# OPAMP_TESTER_1.net
KiCad netlist of a schematic drawn in Altium Designer
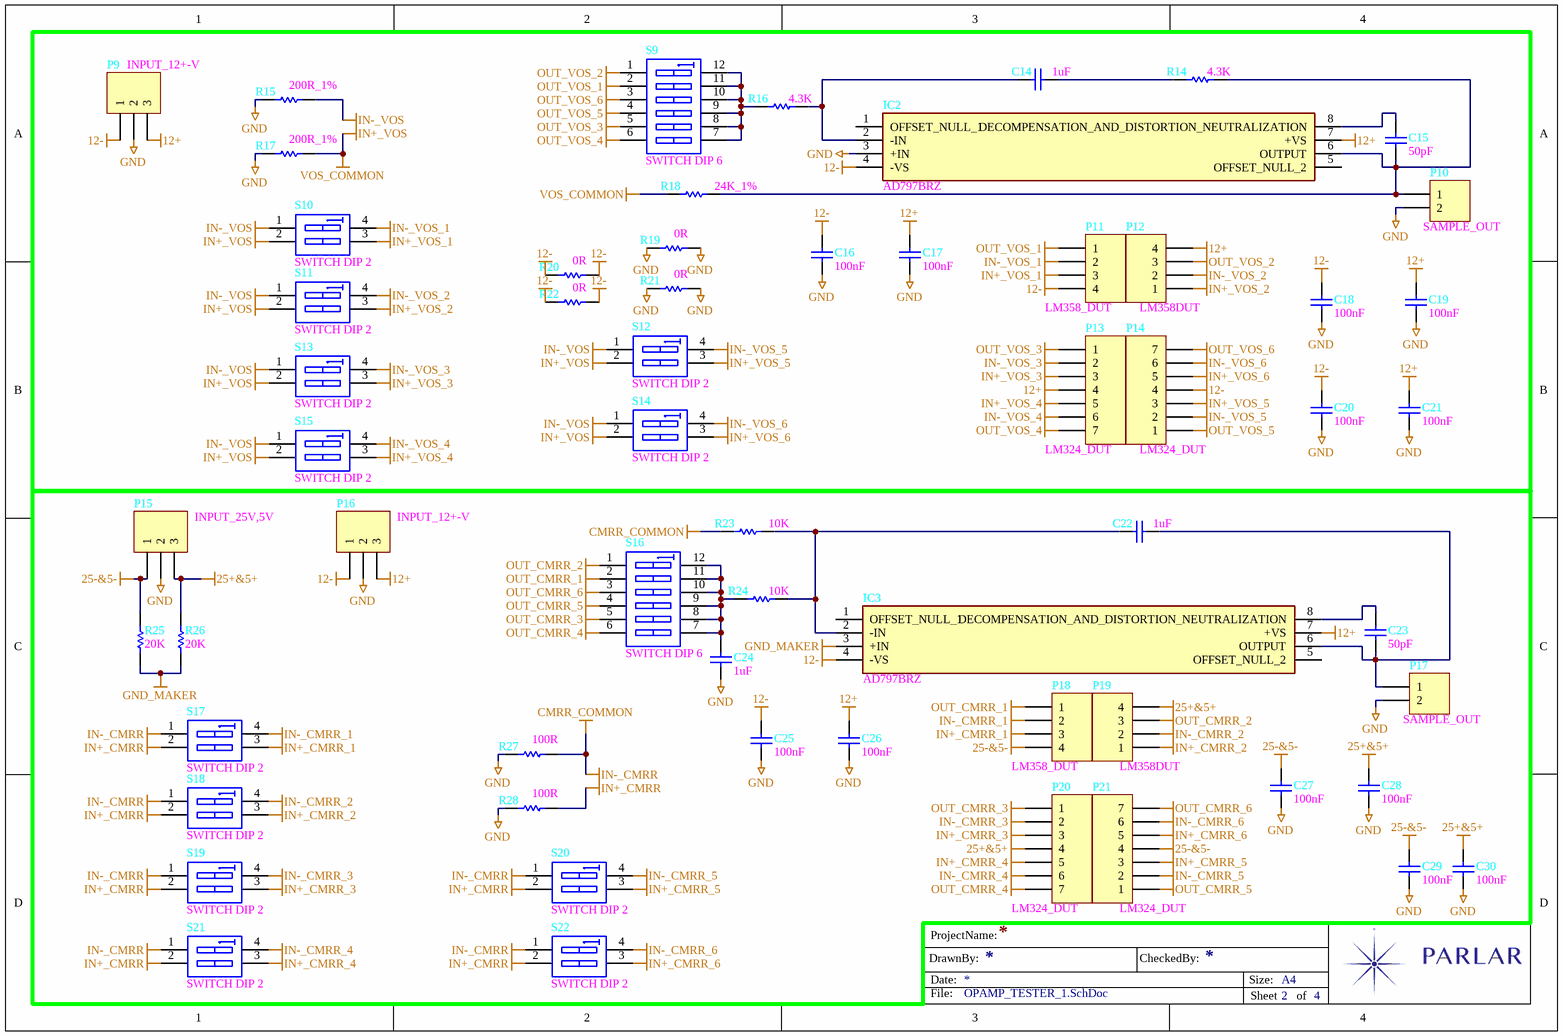
[diagram p0: OPAMP_TESTER_1.SchDoc]

(export (version "E")
  (design (tool "Eeschema 10.0.6"))
  (components
    (comp (ref "C14")
      (value "1uF")
      (footprint "SMD 1206")
      (description "Capacitor")
      (fields (field (name "PUBLISHER") "Altium Limited"))
      (libsource (lib "Parlarlib_30") (part "CAP"))
    )
    (comp (ref "C15")
      (value "50pF")
      (footprint "SMD 1206")
      (description "Capacitor")
      (fields (field (name "PUBLISHER") "Altium Limited"))
      (libsource (lib "Parlarlib_30") (part "CAP"))
    )
    (comp (ref "C16")
      (value "100nF")
      (footprint "SMD 0805")
      (description "Capacitor")
      (fields (field (name "PUBLISHER") "Altium Limited"))
      (libsource (lib "Parlarlib_30") (part "CAP"))
    )
    (comp (ref "C17")
      (value "100nF")
      (footprint "SMD 0805")
      (description "Capacitor")
      (fields (field (name "PUBLISHER") "Altium Limited"))
      (libsource (lib "Parlarlib_30") (part "CAP"))
    )
    (comp (ref "C18")
      (value "100nF")
      (footprint "SMD 0805")
      (description "Capacitor")
      (fields (field (name "PUBLISHER") "Altium Limited"))
      (libsource (lib "Parlarlib_30") (part "CAP"))
    )
    (comp (ref "C19")
      (value "100nF")
      (footprint "SMD 0805")
      (description "Capacitor")
      (fields (field (name "PUBLISHER") "Altium Limited"))
      (libsource (lib "Parlarlib_30") (part "CAP"))
    )
    (comp (ref "C20")
      (value "100nF")
      (footprint "SMD 0805")
      (description "Capacitor")
      (fields (field (name "PUBLISHER") "Altium Limited"))
      (libsource (lib "Parlarlib_30") (part "CAP"))
    )
    (comp (ref "C21")
      (value "100nF")
      (footprint "SMD 0805")
      (description "Capacitor")
      (fields (field (name "PUBLISHER") "Altium Limited"))
      (libsource (lib "Parlarlib_30") (part "CAP"))
    )
    (comp (ref "C22")
      (value "1uF")
      (footprint "SMD 1206")
      (description "Capacitor")
      (fields (field (name "PUBLISHER") "Altium Limited"))
      (libsource (lib "Parlarlib_30") (part "CAP"))
    )
    (comp (ref "C23")
      (value "50pF")
      (footprint "SMD 1206")
      (description "Capacitor")
      (fields (field (name "PUBLISHER") "Altium Limited"))
      (libsource (lib "Parlarlib_30") (part "CAP"))
    )
    (comp (ref "C24")
      (value "1uF")
      (footprint "SMD 0805")
      (description "Capacitor")
      (fields (field (name "PUBLISHER") "Altium Limited"))
      (libsource (lib "Parlarlib_30") (part "CAP"))
    )
    (comp (ref "C25")
      (value "100nF")
      (footprint "SMD 0805")
      (description "Capacitor")
      (fields (field (name "PUBLISHER") "Altium Limited"))
      (libsource (lib "Parlarlib_30") (part "CAP"))
    )
    (comp (ref "C26")
      (value "100nF")
      (footprint "SMD 0805")
      (description "Capacitor")
      (fields (field (name "PUBLISHER") "Altium Limited"))
      (libsource (lib "Parlarlib_30") (part "CAP"))
    )
    (comp (ref "C27")
      (value "100nF")
      (footprint "SMD 0805")
      (description "Capacitor")
      (fields (field (name "PUBLISHER") "Altium Limited"))
      (libsource (lib "Parlarlib_30") (part "CAP"))
    )
    (comp (ref "C28")
      (value "100nF")
      (footprint "SMD 0805")
      (description "Capacitor")
      (fields (field (name "PUBLISHER") "Altium Limited"))
      (libsource (lib "Parlarlib_30") (part "CAP"))
    )
    (comp (ref "C29")
      (value "100nF")
      (footprint "SMD 0805")
      (description "Capacitor")
      (fields (field (name "PUBLISHER") "Altium Limited"))
      (libsource (lib "Parlarlib_30") (part "CAP"))
    )
    (comp (ref "C30")
      (value "100nF")
      (footprint "SMD 0805")
      (description "Capacitor")
      (fields (field (name "PUBLISHER") "Altium Limited"))
      (libsource (lib "Parlarlib_30") (part "CAP"))
    )
    (comp (ref "IC2")
      (value "AD797BRZ")
      (footprint "SamacSys:SOIC127P600X175-8N")
      (description "Integrated Circuit")
      (fields (field (name "MOUSER PART NUMBER") "584-AD797BRZ"))
      (libsource (lib "*") (part "AD797BRZ"))
    )
    (comp (ref "IC3")
      (value "AD797BRZ")
      (footprint "SamacSys:SOIC127P600X175-8N")
      (description "Integrated Circuit")
      (fields (field (name "MOUSER PART NUMBER") "584-AD797BRZ"))
      (libsource (lib "*") (part "AD797BRZ"))
    )
    (comp (ref "P9")
      (value "INPUT_12+-V")
      (footprint "CON XH 3")
      (description "Header, 3-Pin")
      (fields (field (name "PUBLISHER") "Altium Limited"))
      (libsource (lib "Parlarlib_30") (part "CONNECTOR 3"))
    )
    (comp (ref "P10")
      (value "SAMPLE_OUT")
      (footprint "CON XH 2")
      (description "Header, 2-Pin")
      (fields (field (name "PUBLISHER") "Altium Limited"))
      (libsource (lib "Parlarlib_30") (part "CONNECTOR 2"))
    )
    (comp (ref "P11")
      (value "LM358_DUT")
      (footprint "CON HDR 2.54FM 4")
      (description "Header, 4-Pin")
      (fields (field (name "PUBLISHER") "Altium Limited"))
      (libsource (lib "Parlarlib_30") (part "CONNECTOR 4"))
    )
    (comp (ref "P12")
      (value "LM358DUT")
      (footprint "CON HDR 2.54FM 4")
      (description "Header, 4-Pin")
      (fields (field (name "PUBLISHER") "Altium Limited"))
      (libsource (lib "") (part "CONNECTOR 4_1"))
    )
    (comp (ref "P13")
      (value "LM324_DUT")
      (footprint "CON HDR 2.54FM 7")
      (description "Header, 7-Pin")
      (fields (field (name "PUBLISHER") "Altium Limited"))
      (libsource (lib "") (part "CONNECTOR 7_1"))
    )
    (comp (ref "P14")
      (value "LM324_DUT")
      (footprint "CON HDR 2.54FM 7")
      (description "Header, 7-Pin")
      (fields (field (name "PUBLISHER") "Altium Limited"))
      (libsource (lib "Parlarlib_30") (part "CONNECTOR 7"))
    )
    (comp (ref "P15")
      (value "INPUT_25V,5V")
      (footprint "CON XH 3")
      (description "Header, 3-Pin")
      (fields (field (name "PUBLISHER") "Altium Limited"))
      (libsource (lib "Parlarlib_30") (part "CONNECTOR 3"))
    )
    (comp (ref "P16")
      (value "INPUT_12+-V")
      (footprint "CON XH 3")
      (description "Header, 3-Pin")
      (fields (field (name "PUBLISHER") "Altium Limited"))
      (libsource (lib "Parlarlib_30") (part "CONNECTOR 3"))
    )
    (comp (ref "P17")
      (value "SAMPLE_OUT")
      (footprint "CON XH 2")
      (description "Header, 2-Pin")
      (fields (field (name "PUBLISHER") "Altium Limited"))
      (libsource (lib "Parlarlib_30") (part "CONNECTOR 2"))
    )
    (comp (ref "P18")
      (value "LM358_DUT")
      (footprint "CON HDR 2.54FM 4")
      (description "Header, 4-Pin")
      (fields (field (name "PUBLISHER") "Altium Limited"))
      (libsource (lib "Parlarlib_30") (part "CONNECTOR 4"))
    )
    (comp (ref "P19")
      (value "LM358DUT")
      (footprint "CON HDR 2.54FM 4")
      (description "Header, 4-Pin")
      (fields (field (name "PUBLISHER") "Altium Limited"))
      (libsource (lib "") (part "CONNECTOR 4_1"))
    )
    (comp (ref "P20")
      (value "LM324_DUT")
      (footprint "CON HDR 2.54FM 7")
      (description "Header, 7-Pin")
      (fields (field (name "PUBLISHER") "Altium Limited"))
      (libsource (lib "") (part "CONNECTOR 7_1"))
    )
    (comp (ref "P21")
      (value "LM324_DUT")
      (footprint "CON HDR 2.54FM 7")
      (description "Header, 7-Pin")
      (fields (field (name "PUBLISHER") "Altium Limited"))
      (libsource (lib "Parlarlib_30") (part "CONNECTOR 7"))
    )
    (comp (ref "R14")
      (value "4.3K")
      (footprint "SMD 0805")
      (description "Resistor")
      (libsource (lib "Parlarlib_30") (part "RES"))
    )
    (comp (ref "R15")
      (value "200R_1%")
      (footprint "SMD 0805")
      (description "Resistor")
      (libsource (lib "Parlarlib_30") (part "RES"))
    )
    (comp (ref "R16")
      (value "4.3K")
      (footprint "SMD 1206")
      (description "Resistor")
      (libsource (lib "Parlarlib_30") (part "RES"))
    )
    (comp (ref "R17")
      (value "200R_1%")
      (footprint "SMD 0805")
      (description "Resistor")
      (libsource (lib "Parlarlib_30") (part "RES"))
    )
    (comp (ref "R18")
      (value "24K_1%")
      (footprint "SMD 0805")
      (description "Resistor")
      (libsource (lib "Parlarlib_30") (part "RES"))
    )
    (comp (ref "R19")
      (value "0R")
      (footprint "SMD 1206")
      (description "Resistor")
      (libsource (lib "Parlarlib_30") (part "RES"))
    )
    (comp (ref "R20")
      (value "0R")
      (footprint "SMD 1206")
      (description "Resistor")
      (libsource (lib "Parlarlib_30") (part "RES"))
    )
    (comp (ref "R21")
      (value "0R")
      (footprint "SMD 1206")
      (description "Resistor")
      (libsource (lib "Parlarlib_30") (part "RES"))
    )
    (comp (ref "R22")
      (value "0R")
      (footprint "SMD 1206")
      (description "Resistor")
      (libsource (lib "Parlarlib_30") (part "RES"))
    )
    (comp (ref "R23")
      (value "10K")
      (footprint "SMD 0805")
      (description "Resistor")
      (libsource (lib "Parlarlib_30") (part "RES"))
    )
    (comp (ref "R24")
      (value "10K")
      (footprint "SMD 0805")
      (description "Resistor")
      (libsource (lib "Parlarlib_30") (part "RES"))
    )
    (comp (ref "R25")
      (value "20K")
      (footprint "SMD 0805")
      (description "Resistor")
      (libsource (lib "Parlarlib_30") (part "RES"))
    )
    (comp (ref "R26")
      (value "20K")
      (footprint "SMD 0805")
      (description "Resistor")
      (libsource (lib "Parlarlib_30") (part "RES"))
    )
    (comp (ref "R27")
      (value "100R")
      (footprint "SMD 0805")
      (description "Resistor")
      (libsource (lib "Parlarlib_30") (part "RES"))
    )
    (comp (ref "R28")
      (value "100R")
      (footprint "SMD 0805")
      (description "Resistor")
      (libsource (lib "Parlarlib_30") (part "RES"))
    )
    (comp (ref "S9")
      (value "SWITCH DIP 6")
      (footprint "SWITCH DIP 6")
      (description "DIP Switch, 6 Position, SPST")
      (fields (field (name "PUBLISHER") "Altium Limited"))
      (libsource (lib "Parlarlib_30") (part "SWITCH DIP 6"))
    )
    (comp (ref "S10")
      (value "SWITCH DIP 2")
      (footprint "SWITCH DIP 2")
      (description "DIP Switch, 2 Position, SPST")
      (fields (field (name "PUBLISHER") "Altium Limited"))
      (libsource (lib "Parlarlib_30") (part "SWITCH DIP 2"))
    )
    (comp (ref "S11")
      (value "SWITCH DIP 2")
      (footprint "SWITCH DIP 2")
      (description "DIP Switch, 2 Position, SPST")
      (fields (field (name "PUBLISHER") "Altium Limited"))
      (libsource (lib "Parlarlib_30") (part "SWITCH DIP 2"))
    )
    (comp (ref "S12")
      (value "SWITCH DIP 2")
      (footprint "SWITCH DIP 2")
      (description "DIP Switch, 2 Position, SPST")
      (fields (field (name "PUBLISHER") "Altium Limited"))
      (libsource (lib "Parlarlib_30") (part "SWITCH DIP 2"))
    )
    (comp (ref "S13")
      (value "SWITCH DIP 2")
      (footprint "SWITCH DIP 2")
      (description "DIP Switch, 2 Position, SPST")
      (fields (field (name "PUBLISHER") "Altium Limited"))
      (libsource (lib "Parlarlib_30") (part "SWITCH DIP 2"))
    )
    (comp (ref "S14")
      (value "SWITCH DIP 2")
      (footprint "SWITCH DIP 2")
      (description "DIP Switch, 2 Position, SPST")
      (fields (field (name "PUBLISHER") "Altium Limited"))
      (libsource (lib "Parlarlib_30") (part "SWITCH DIP 2"))
    )
    (comp (ref "S15")
      (value "SWITCH DIP 2")
      (footprint "SWITCH DIP 2")
      (description "DIP Switch, 2 Position, SPST")
      (fields (field (name "PUBLISHER") "Altium Limited"))
      (libsource (lib "Parlarlib_30") (part "SWITCH DIP 2"))
    )
    (comp (ref "S16")
      (value "SWITCH DIP 6")
      (footprint "SWITCH DIP 6")
      (description "DIP Switch, 6 Position, SPST")
      (fields (field (name "PUBLISHER") "Altium Limited"))
      (libsource (lib "Parlarlib_30") (part "SWITCH DIP 6"))
    )
    (comp (ref "S17")
      (value "SWITCH DIP 2")
      (footprint "SWITCH DIP 2")
      (description "DIP Switch, 2 Position, SPST")
      (fields (field (name "PUBLISHER") "Altium Limited"))
      (libsource (lib "Parlarlib_30") (part "SWITCH DIP 2"))
    )
    (comp (ref "S18")
      (value "SWITCH DIP 2")
      (footprint "SWITCH DIP 2")
      (description "DIP Switch, 2 Position, SPST")
      (fields (field (name "PUBLISHER") "Altium Limited"))
      (libsource (lib "Parlarlib_30") (part "SWITCH DIP 2"))
    )
    (comp (ref "S19")
      (value "SWITCH DIP 2")
      (footprint "SWITCH DIP 2")
      (description "DIP Switch, 2 Position, SPST")
      (fields (field (name "PUBLISHER") "Altium Limited"))
      (libsource (lib "Parlarlib_30") (part "SWITCH DIP 2"))
    )
    (comp (ref "S20")
      (value "SWITCH DIP 2")
      (footprint "SWITCH DIP 2")
      (description "DIP Switch, 2 Position, SPST")
      (fields (field (name "PUBLISHER") "Altium Limited"))
      (libsource (lib "Parlarlib_30") (part "SWITCH DIP 2"))
    )
    (comp (ref "S21")
      (value "SWITCH DIP 2")
      (footprint "SWITCH DIP 2")
      (description "DIP Switch, 2 Position, SPST")
      (fields (field (name "PUBLISHER") "Altium Limited"))
      (libsource (lib "Parlarlib_30") (part "SWITCH DIP 2"))
    )
    (comp (ref "S22")
      (value "SWITCH DIP 2")
      (footprint "SWITCH DIP 2")
      (description "DIP Switch, 2 Position, SPST")
      (fields (field (name "PUBLISHER") "Altium Limited"))
      (libsource (lib "Parlarlib_30") (part "SWITCH DIP 2"))
    )
  )
  (nets
    (net (code "1") (name "12+") (class "Default")
      (node (ref "C17") (pin "2") (pinfunction "2_2") (pintype "passive"))
      (node (ref "C19") (pin "2") (pinfunction "2_2") (pintype "passive"))
      (node (ref "C21") (pin "2") (pinfunction "2_2") (pintype "passive"))
      (node (ref "C26") (pin "2") (pinfunction "2_2") (pintype "passive"))
      (node (ref "IC2") (pin "7") (pinfunction "+VS_7") (pintype "passive"))
      (node (ref "IC3") (pin "7") (pinfunction "+VS_7") (pintype "passive"))
      (node (ref "P12") (pin "4") (pinfunction "4_4") (pintype "passive"))
      (node (ref "P13") (pin "4") (pinfunction "4_4") (pintype "passive"))
      (node (ref "P16") (pin "3") (pinfunction "3_3") (pintype "passive"))
      (node (ref "P9") (pin "3") (pinfunction "3_3") (pintype "passive"))
    )
    (net (code "2") (name "12-") (class "Default")
      (node (ref "C16") (pin "2") (pinfunction "2_2") (pintype "passive"))
      (node (ref "C18") (pin "2") (pinfunction "2_2") (pintype "passive"))
      (node (ref "C20") (pin "2") (pinfunction "2_2") (pintype "passive"))
      (node (ref "C25") (pin "2") (pinfunction "2_2") (pintype "passive"))
      (node (ref "IC2") (pin "4") (pinfunction "-VS_4") (pintype "passive"))
      (node (ref "IC3") (pin "4") (pinfunction "-VS_4") (pintype "passive"))
      (node (ref "P11") (pin "4") (pinfunction "4_4") (pintype "passive"))
      (node (ref "P14") (pin "4") (pinfunction "4_4") (pintype "passive"))
      (node (ref "P16") (pin "1") (pinfunction "1_1") (pintype "passive"))
      (node (ref "P9") (pin "1") (pinfunction "1_1") (pintype "passive"))
      (node (ref "R20") (pin "1") (pinfunction "1_1") (pintype "passive"))
      (node (ref "R20") (pin "2") (pinfunction "2_2") (pintype "passive"))
      (node (ref "R22") (pin "1") (pinfunction "1_1") (pintype "passive"))
      (node (ref "R22") (pin "2") (pinfunction "2_2") (pintype "passive"))
    )
    (net (code "3") (name "25+&5+") (class "Default")
      (node (ref "C28") (pin "2") (pinfunction "2_2") (pintype "passive"))
      (node (ref "C30") (pin "2") (pinfunction "2_2") (pintype "passive"))
      (node (ref "P15") (pin "3") (pinfunction "3_3") (pintype "passive"))
      (node (ref "P19") (pin "4") (pinfunction "4_4") (pintype "passive"))
      (node (ref "P20") (pin "4") (pinfunction "4_4") (pintype "passive"))
      (node (ref "R26") (pin "2") (pinfunction "2_2") (pintype "passive"))
    )
    (net (code "4") (name "25-&5-") (class "Default")
      (node (ref "C27") (pin "2") (pinfunction "2_2") (pintype "passive"))
      (node (ref "C29") (pin "2") (pinfunction "2_2") (pintype "passive"))
      (node (ref "P15") (pin "1") (pinfunction "1_1") (pintype "passive"))
      (node (ref "P18") (pin "4") (pinfunction "4_4") (pintype "passive"))
      (node (ref "P21") (pin "4") (pinfunction "4_4") (pintype "passive"))
      (node (ref "R25") (pin "2") (pinfunction "2_2") (pintype "passive"))
    )
    (net (code "5") (name "CMRR_COMMON") (class "Default")
      (node (ref "R23") (pin "1") (pinfunction "1_1") (pintype "passive"))
      (node (ref "R27") (pin "2") (pinfunction "2_2") (pintype "passive"))
      (node (ref "S17") (pin "1") (pinfunction "A1_1") (pintype "passive"))
      (node (ref "S18") (pin "1") (pinfunction "A1_1") (pintype "passive"))
      (node (ref "S19") (pin "1") (pinfunction "A1_1") (pintype "passive"))
      (node (ref "S20") (pin "1") (pinfunction "A1_1") (pintype "passive"))
      (node (ref "S21") (pin "1") (pinfunction "A1_1") (pintype "passive"))
      (node (ref "S22") (pin "1") (pinfunction "A1_1") (pintype "passive"))
    )
    (net (code "6") (name "GND") (class "Default")
      (node (ref "C16") (pin "1") (pinfunction "1_1") (pintype "passive"))
      (node (ref "C17") (pin "1") (pinfunction "1_1") (pintype "passive"))
      (node (ref "C18") (pin "1") (pinfunction "1_1") (pintype "passive"))
      (node (ref "C19") (pin "1") (pinfunction "1_1") (pintype "passive"))
      (node (ref "C20") (pin "1") (pinfunction "1_1") (pintype "passive"))
      (node (ref "C21") (pin "1") (pinfunction "1_1") (pintype "passive"))
      (node (ref "C24") (pin "1") (pinfunction "1_1") (pintype "passive"))
      (node (ref "C25") (pin "1") (pinfunction "1_1") (pintype "passive"))
      (node (ref "C26") (pin "1") (pinfunction "1_1") (pintype "passive"))
      (node (ref "C27") (pin "1") (pinfunction "1_1") (pintype "passive"))
      (node (ref "C28") (pin "1") (pinfunction "1_1") (pintype "passive"))
      (node (ref "C29") (pin "1") (pinfunction "1_1") (pintype "passive"))
      (node (ref "C30") (pin "1") (pinfunction "1_1") (pintype "passive"))
      (node (ref "IC2") (pin "3") (pinfunction "+IN_3") (pintype "passive"))
      (node (ref "P10") (pin "2") (pinfunction "2_2") (pintype "passive"))
      (node (ref "P15") (pin "2") (pinfunction "2_2") (pintype "passive"))
      (node (ref "P16") (pin "2") (pinfunction "2_2") (pintype "passive"))
      (node (ref "P17") (pin "2") (pinfunction "2_2") (pintype "passive"))
      (node (ref "P9") (pin "2") (pinfunction "2_2") (pintype "passive"))
      (node (ref "R15") (pin "1") (pinfunction "1_1") (pintype "passive"))
      (node (ref "R17") (pin "1") (pinfunction "1_1") (pintype "passive"))
      (node (ref "R19") (pin "1") (pinfunction "1_1") (pintype "passive"))
      (node (ref "R19") (pin "2") (pinfunction "2_2") (pintype "passive"))
      (node (ref "R21") (pin "1") (pinfunction "1_1") (pintype "passive"))
      (node (ref "R21") (pin "2") (pinfunction "2_2") (pintype "passive"))
      (node (ref "R27") (pin "1") (pinfunction "1_1") (pintype "passive"))
      (node (ref "R28") (pin "1") (pinfunction "1_1") (pintype "passive"))
    )
    (net (code "7") (name "GND_MAKER") (class "Default")
      (node (ref "IC3") (pin "3") (pinfunction "+IN_3") (pintype "passive"))
      (node (ref "R25") (pin "1") (pinfunction "1_1") (pintype "passive"))
      (node (ref "R26") (pin "1") (pinfunction "1_1") (pintype "passive"))
    )
    (net (code "8") (name "IN+_CMRR") (class "Default")
      (node (ref "R28") (pin "2") (pinfunction "2_2") (pintype "passive"))
      (node (ref "S17") (pin "2") (pinfunction "A2_2") (pintype "passive"))
      (node (ref "S18") (pin "2") (pinfunction "A2_2") (pintype "passive"))
      (node (ref "S19") (pin "2") (pinfunction "A2_2") (pintype "passive"))
      (node (ref "S20") (pin "2") (pinfunction "A2_2") (pintype "passive"))
      (node (ref "S21") (pin "2") (pinfunction "A2_2") (pintype "passive"))
      (node (ref "S22") (pin "2") (pinfunction "A2_2") (pintype "passive"))
    )
    (net (code "9") (name "IN+_CMRR_1") (class "Default")
      (node (ref "P18") (pin "3") (pinfunction "3_3") (pintype "passive"))
      (node (ref "S17") (pin "3") (pinfunction "B2_3") (pintype "passive"))
    )
    (net (code "10") (name "IN+_CMRR_2") (class "Default")
      (node (ref "P19") (pin "1") (pinfunction "1_1") (pintype "passive"))
      (node (ref "S18") (pin "3") (pinfunction "B2_3") (pintype "passive"))
    )
    (net (code "11") (name "IN+_CMRR_3") (class "Default")
      (node (ref "P20") (pin "3") (pinfunction "3_3") (pintype "passive"))
      (node (ref "S19") (pin "3") (pinfunction "B2_3") (pintype "passive"))
    )
    (net (code "12") (name "IN+_CMRR_4") (class "Default")
      (node (ref "P20") (pin "5") (pinfunction "5_5") (pintype "passive"))
      (node (ref "S21") (pin "3") (pinfunction "B2_3") (pintype "passive"))
    )
    (net (code "13") (name "IN+_CMRR_5") (class "Default")
      (node (ref "P21") (pin "3") (pinfunction "3_3") (pintype "passive"))
      (node (ref "S20") (pin "3") (pinfunction "B2_3") (pintype "passive"))
    )
    (net (code "14") (name "IN+_CMRR_6") (class "Default")
      (node (ref "P21") (pin "5") (pinfunction "5_5") (pintype "passive"))
      (node (ref "S22") (pin "3") (pinfunction "B2_3") (pintype "passive"))
    )
    (net (code "15") (name "IN+_VOS") (class "Default")
      (node (ref "R17") (pin "2") (pinfunction "2_2") (pintype "passive"))
      (node (ref "R18") (pin "1") (pinfunction "1_1") (pintype "passive"))
      (node (ref "S10") (pin "2") (pinfunction "A2_2") (pintype "passive"))
      (node (ref "S11") (pin "2") (pinfunction "A2_2") (pintype "passive"))
      (node (ref "S12") (pin "2") (pinfunction "A2_2") (pintype "passive"))
      (node (ref "S13") (pin "2") (pinfunction "A2_2") (pintype "passive"))
      (node (ref "S14") (pin "2") (pinfunction "A2_2") (pintype "passive"))
      (node (ref "S15") (pin "2") (pinfunction "A2_2") (pintype "passive"))
    )
    (net (code "16") (name "IN+_VOS_1") (class "Default")
      (node (ref "P11") (pin "3") (pinfunction "3_3") (pintype "passive"))
      (node (ref "S10") (pin "3") (pinfunction "B2_3") (pintype "passive"))
    )
    (net (code "17") (name "IN+_VOS_2") (class "Default")
      (node (ref "P12") (pin "1") (pinfunction "1_1") (pintype "passive"))
      (node (ref "S11") (pin "3") (pinfunction "B2_3") (pintype "passive"))
    )
    (net (code "18") (name "IN+_VOS_3") (class "Default")
      (node (ref "P13") (pin "3") (pinfunction "3_3") (pintype "passive"))
      (node (ref "S13") (pin "3") (pinfunction "B2_3") (pintype "passive"))
    )
    (net (code "19") (name "IN+_VOS_4") (class "Default")
      (node (ref "P13") (pin "5") (pinfunction "5_5") (pintype "passive"))
      (node (ref "S15") (pin "3") (pinfunction "B2_3") (pintype "passive"))
    )
    (net (code "20") (name "IN+_VOS_5") (class "Default")
      (node (ref "P14") (pin "3") (pinfunction "3_3") (pintype "passive"))
      (node (ref "S12") (pin "3") (pinfunction "B2_3") (pintype "passive"))
    )
    (net (code "21") (name "IN+_VOS_6") (class "Default")
      (node (ref "P14") (pin "5") (pinfunction "5_5") (pintype "passive"))
      (node (ref "S14") (pin "3") (pinfunction "B2_3") (pintype "passive"))
    )
    (net (code "22") (name "IN-_CMRR_1") (class "Default")
      (node (ref "P18") (pin "2") (pinfunction "2_2") (pintype "passive"))
      (node (ref "S17") (pin "4") (pinfunction "B1_4") (pintype "passive"))
    )
    (net (code "23") (name "IN-_CMRR_2") (class "Default")
      (node (ref "P19") (pin "2") (pinfunction "2_2") (pintype "passive"))
      (node (ref "S18") (pin "4") (pinfunction "B1_4") (pintype "passive"))
    )
    (net (code "24") (name "IN-_CMRR_3") (class "Default")
      (node (ref "P20") (pin "2") (pinfunction "2_2") (pintype "passive"))
      (node (ref "S19") (pin "4") (pinfunction "B1_4") (pintype "passive"))
    )
    (net (code "25") (name "IN-_CMRR_4") (class "Default")
      (node (ref "P20") (pin "6") (pinfunction "6_6") (pintype "passive"))
      (node (ref "S21") (pin "4") (pinfunction "B1_4") (pintype "passive"))
    )
    (net (code "26") (name "IN-_CMRR_5") (class "Default")
      (node (ref "P21") (pin "2") (pinfunction "2_2") (pintype "passive"))
      (node (ref "S20") (pin "4") (pinfunction "B1_4") (pintype "passive"))
    )
    (net (code "27") (name "IN-_CMRR_6") (class "Default")
      (node (ref "P21") (pin "6") (pinfunction "6_6") (pintype "passive"))
      (node (ref "S22") (pin "4") (pinfunction "B1_4") (pintype "passive"))
    )
    (net (code "28") (name "IN-_VOS") (class "Default")
      (node (ref "R15") (pin "2") (pinfunction "2_2") (pintype "passive"))
      (node (ref "S10") (pin "1") (pinfunction "A1_1") (pintype "passive"))
      (node (ref "S11") (pin "1") (pinfunction "A1_1") (pintype "passive"))
      (node (ref "S12") (pin "1") (pinfunction "A1_1") (pintype "passive"))
      (node (ref "S13") (pin "1") (pinfunction "A1_1") (pintype "passive"))
      (node (ref "S14") (pin "1") (pinfunction "A1_1") (pintype "passive"))
      (node (ref "S15") (pin "1") (pinfunction "A1_1") (pintype "passive"))
    )
    (net (code "29") (name "IN-_VOS_1") (class "Default")
      (node (ref "P11") (pin "2") (pinfunction "2_2") (pintype "passive"))
      (node (ref "S10") (pin "4") (pinfunction "B1_4") (pintype "passive"))
    )
    (net (code "30") (name "IN-_VOS_2") (class "Default")
      (node (ref "P12") (pin "2") (pinfunction "2_2") (pintype "passive"))
      (node (ref "S11") (pin "4") (pinfunction "B1_4") (pintype "passive"))
    )
    (net (code "31") (name "IN-_VOS_3") (class "Default")
      (node (ref "P13") (pin "2") (pinfunction "2_2") (pintype "passive"))
      (node (ref "S13") (pin "4") (pinfunction "B1_4") (pintype "passive"))
    )
    (net (code "32") (name "IN-_VOS_4") (class "Default")
      (node (ref "P13") (pin "6") (pinfunction "6_6") (pintype "passive"))
      (node (ref "S15") (pin "4") (pinfunction "B1_4") (pintype "passive"))
    )
    (net (code "33") (name "IN-_VOS_5") (class "Default")
      (node (ref "P14") (pin "2") (pinfunction "2_2") (pintype "passive"))
      (node (ref "S12") (pin "4") (pinfunction "B1_4") (pintype "passive"))
    )
    (net (code "34") (name "IN-_VOS_6") (class "Default")
      (node (ref "P14") (pin "6") (pinfunction "6_6") (pintype "passive"))
      (node (ref "S14") (pin "4") (pinfunction "B1_4") (pintype "passive"))
    )
    (net (code "35") (name "Net-(C14-Pad1)") (class "Default")
      (node (ref "C14") (pin "1") (pinfunction "1_1") (pintype "passive"))
      (node (ref "R14") (pin "1") (pinfunction "1_1") (pintype "passive"))
    )
    (net (code "36") (name "Net-(IC2--IN)") (class "Default")
      (node (ref "C14") (pin "2") (pinfunction "2_2") (pintype "passive"))
      (node (ref "IC2") (pin "2") (pinfunction "-IN_2") (pintype "passive"))
      (node (ref "R16") (pin "2") (pinfunction "2_2") (pintype "passive"))
    )
    (net (code "37") (name "Net-(IC2-DECOMPENSATION_AND_DISTORTION_NEUTRALIZATION)") (class "Default")
      (node (ref "C15") (pin "1") (pinfunction "1_1") (pintype "passive"))
      (node (ref "IC2") (pin "8") (pinfunction "DECOMPENSATION_AND_DISTORTION_NEUTRALIZATION_8") (pintype "passive"))
    )
    (net (code "38") (name "Net-(IC2-OUTPUT)") (class "Default")
      (node (ref "C15") (pin "2") (pinfunction "2_2") (pintype "passive"))
      (node (ref "IC2") (pin "6") (pinfunction "OUTPUT_6") (pintype "passive"))
      (node (ref "P10") (pin "1") (pinfunction "1_1") (pintype "passive"))
      (node (ref "R14") (pin "2") (pinfunction "2_2") (pintype "passive"))
      (node (ref "R18") (pin "2") (pinfunction "2_2") (pintype "passive"))
    )
    (net (code "39") (name "Net-(IC3--IN)") (class "Default")
      (node (ref "C22") (pin "2") (pinfunction "2_2") (pintype "passive"))
      (node (ref "IC3") (pin "2") (pinfunction "-IN_2") (pintype "passive"))
      (node (ref "R23") (pin "2") (pinfunction "2_2") (pintype "passive"))
      (node (ref "R24") (pin "2") (pinfunction "2_2") (pintype "passive"))
    )
    (net (code "40") (name "Net-(IC3-DECOMPENSATION_AND_DISTORTION_NEUTRALIZATION)") (class "Default")
      (node (ref "C23") (pin "1") (pinfunction "1_1") (pintype "passive"))
      (node (ref "IC3") (pin "8") (pinfunction "DECOMPENSATION_AND_DISTORTION_NEUTRALIZATION_8") (pintype "passive"))
    )
    (net (code "41") (name "Net-(IC3-OUTPUT)") (class "Default")
      (node (ref "C22") (pin "1") (pinfunction "1_1") (pintype "passive"))
      (node (ref "C23") (pin "2") (pinfunction "2_2") (pintype "passive"))
      (node (ref "IC3") (pin "6") (pinfunction "OUTPUT_6") (pintype "passive"))
      (node (ref "P17") (pin "1") (pinfunction "1_1") (pintype "passive"))
    )
    (net (code "42") (name "Net-(S9-B1)") (class "Default")
      (node (ref "R16") (pin "1") (pinfunction "1_1") (pintype "passive"))
      (node (ref "S9") (pin "10") (pinfunction "B3_10") (pintype "passive"))
      (node (ref "S9") (pin "11") (pinfunction "B2_11") (pintype "passive"))
      (node (ref "S9") (pin "12") (pinfunction "B1_12") (pintype "passive"))
      (node (ref "S9") (pin "7") (pinfunction "B6_7") (pintype "passive"))
      (node (ref "S9") (pin "8") (pinfunction "B5_8") (pintype "passive"))
      (node (ref "S9") (pin "9") (pinfunction "B4_9") (pintype "passive"))
    )
    (net (code "43") (name "Net-(S16-B1)") (class "Default")
      (node (ref "C24") (pin "2") (pinfunction "2_2") (pintype "passive"))
      (node (ref "R24") (pin "1") (pinfunction "1_1") (pintype "passive"))
      (node (ref "S16") (pin "10") (pinfunction "B3_10") (pintype "passive"))
      (node (ref "S16") (pin "11") (pinfunction "B2_11") (pintype "passive"))
      (node (ref "S16") (pin "12") (pinfunction "B1_12") (pintype "passive"))
      (node (ref "S16") (pin "7") (pinfunction "B6_7") (pintype "passive"))
      (node (ref "S16") (pin "8") (pinfunction "B5_8") (pintype "passive"))
      (node (ref "S16") (pin "9") (pinfunction "B4_9") (pintype "passive"))
    )
    (net (code "44") (name "OUT_CMRR_1") (class "Default")
      (node (ref "P18") (pin "1") (pinfunction "1_1") (pintype "passive"))
      (node (ref "S16") (pin "2") (pinfunction "A2_2") (pintype "passive"))
    )
    (net (code "45") (name "OUT_CMRR_2") (class "Default")
      (node (ref "P19") (pin "3") (pinfunction "3_3") (pintype "passive"))
      (node (ref "S16") (pin "1") (pinfunction "A1_1") (pintype "passive"))
    )
    (net (code "46") (name "OUT_CMRR_3") (class "Default")
      (node (ref "P20") (pin "1") (pinfunction "1_1") (pintype "passive"))
      (node (ref "S16") (pin "5") (pinfunction "A5_5") (pintype "passive"))
    )
    (net (code "47") (name "OUT_CMRR_4") (class "Default")
      (node (ref "P20") (pin "7") (pinfunction "7_7") (pintype "passive"))
      (node (ref "S16") (pin "6") (pinfunction "A6_6") (pintype "passive"))
    )
    (net (code "48") (name "OUT_CMRR_5") (class "Default")
      (node (ref "P21") (pin "1") (pinfunction "1_1") (pintype "passive"))
      (node (ref "S16") (pin "4") (pinfunction "A4_4") (pintype "passive"))
    )
    (net (code "49") (name "OUT_CMRR_6") (class "Default")
      (node (ref "P21") (pin "7") (pinfunction "7_7") (pintype "passive"))
      (node (ref "S16") (pin "3") (pinfunction "A3_3") (pintype "passive"))
    )
    (net (code "50") (name "OUT_VOS_1") (class "Default")
      (node (ref "P11") (pin "1") (pinfunction "1_1") (pintype "passive"))
      (node (ref "S9") (pin "2") (pinfunction "A2_2") (pintype "passive"))
    )
    (net (code "51") (name "OUT_VOS_2") (class "Default")
      (node (ref "P12") (pin "3") (pinfunction "3_3") (pintype "passive"))
      (node (ref "S9") (pin "1") (pinfunction "A1_1") (pintype "passive"))
    )
    (net (code "52") (name "OUT_VOS_3") (class "Default")
      (node (ref "P13") (pin "1") (pinfunction "1_1") (pintype "passive"))
      (node (ref "S9") (pin "5") (pinfunction "A5_5") (pintype "passive"))
    )
    (net (code "53") (name "OUT_VOS_4") (class "Default")
      (node (ref "P13") (pin "7") (pinfunction "7_7") (pintype "passive"))
      (node (ref "S9") (pin "6") (pinfunction "A6_6") (pintype "passive"))
    )
    (net (code "54") (name "OUT_VOS_5") (class "Default")
      (node (ref "P14") (pin "1") (pinfunction "1_1") (pintype "passive"))
      (node (ref "S9") (pin "4") (pinfunction "A4_4") (pintype "passive"))
    )
    (net (code "55") (name "OUT_VOS_6") (class "Default")
      (node (ref "P14") (pin "7") (pinfunction "7_7") (pintype "passive"))
      (node (ref "S9") (pin "3") (pinfunction "A3_3") (pintype "passive"))
    )
    (net (code "56") (name "unconnected-(IC2-OFFSET_NULL_1-Pad1)") (class "Default")
      (node (ref "IC2") (pin "1") (pinfunction "OFFSET_NULL_1_1") (pintype "passive"))
    )
    (net (code "57") (name "unconnected-(IC2-OFFSET_NULL_2-Pad5)") (class "Default")
      (node (ref "IC2") (pin "5") (pinfunction "OFFSET_NULL_2_5") (pintype "passive"))
    )
    (net (code "58") (name "unconnected-(IC3-OFFSET_NULL_1-Pad1)") (class "Default")
      (node (ref "IC3") (pin "1") (pinfunction "OFFSET_NULL_1_1") (pintype "passive"))
    )
    (net (code "59") (name "unconnected-(IC3-OFFSET_NULL_2-Pad5)") (class "Default")
      (node (ref "IC3") (pin "5") (pinfunction "OFFSET_NULL_2_5") (pintype "passive"))
    )
  )
)
